# basic-inline-turbidimeter_power_board.net
KiCad netlist of a schematic drawn in EAGLE
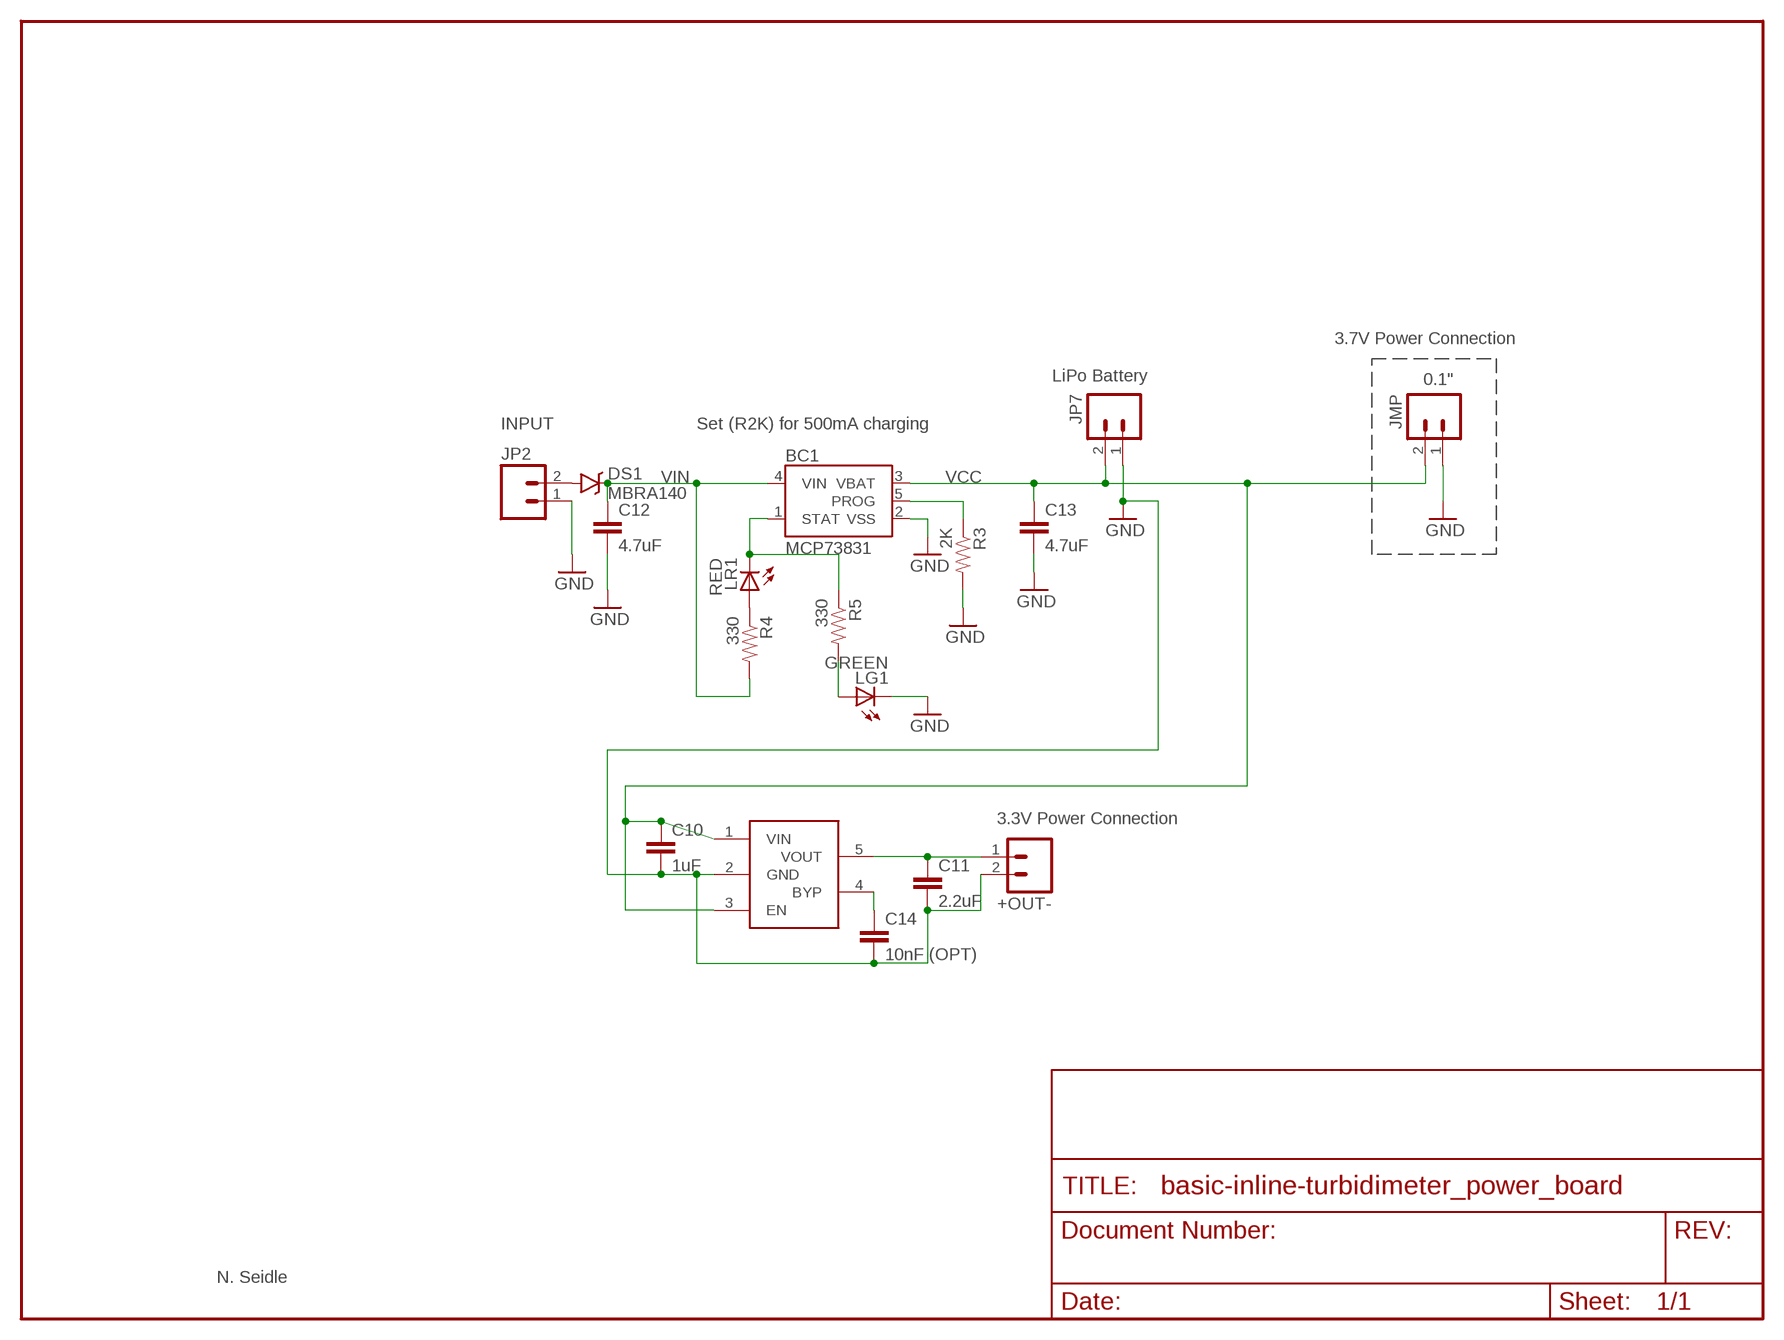
[diagram p0: schematic, sheet 1]

(export (version "E")
  (design (tool "Eeschema 10.0.6"))
  (components
    (comp (ref "+OUT-")
      (value "M02PTH")
      (footprint "eagle-import:1X02")
      (libsource (lib "eagle-import") (part "SparkFun-Connectors_M02PTH"))
    )
    (comp (ref "BC1")
      (value "MCP73831")
      (footprint "eagle-import:SOT23-5")
      (libsource (lib "eagle-import") (part "MCP73831"))
    )
    (comp (ref "C10")
      (value "1uF")
      (footprint "eagle-import:0603-CAP")
      (libsource (lib "eagle-import") (part "SparkFun-Passives_CAP0603-CAP"))
    )
    (comp (ref "C11")
      (value "2.2uF")
      (footprint "eagle-import:0603-CAP")
      (libsource (lib "eagle-import") (part "SparkFun-Passives_CAP0603-CAP"))
    )
    (comp (ref "C12")
      (value "4.7uF")
      (footprint "eagle-import:0402-CAP")
      (libsource (lib "eagle-import") (part "CAP0402-CAP"))
    )
    (comp (ref "C13")
      (value "4.7uF")
      (footprint "eagle-import:0402-CAP")
      (libsource (lib "eagle-import") (part "CAP0402-CAP"))
    )
    (comp (ref "C14")
      (value "10nF (OPT)")
      (footprint "eagle-import:0603-CAP")
      (libsource (lib "eagle-import") (part "SparkFun-Passives_CAP0603-CAP"))
    )
    (comp (ref "DS1")
      (value "MBRA140")
      (footprint "eagle-import:SMA-DIODE")
      (libsource (lib "eagle-import") (part "MBRA140"))
    )
    (comp (ref "JMP")
      (value "M02PTH")
      (footprint "eagle-import:1X02")
      (libsource (lib "eagle-import") (part "M02PTH"))
    )
    (comp (ref "JP2")
      (value "M02PTH")
      (footprint "eagle-import:1X02")
      (libsource (lib "eagle-import") (part "SparkFun-Connectors_M02PTH"))
    )
    (comp (ref "JP7")
      (value "LiPo Battery")
      (footprint "eagle-import:JST-2-SMD")
      (libsource (lib "eagle-import") (part "M02-JST-2MM-SMT"))
    )
    (comp (ref "LG1")
      (value "GREEN")
      (footprint "eagle-import:LED-0603")
      (libsource (lib "eagle-import") (part "LED0603"))
    )
    (comp (ref "LR1")
      (value "RED")
      (footprint "eagle-import:LED-0603")
      (libsource (lib "eagle-import") (part "LED0603"))
    )
    (comp (ref "R3")
      (value "2K")
      (footprint "eagle-import:0402-RES")
      (libsource (lib "eagle-import") (part "RESISTOR0402-RES"))
    )
    (comp (ref "R4")
      (value "330")
      (footprint "eagle-import:0402-RES")
      (libsource (lib "eagle-import") (part "RESISTOR0402-RES"))
    )
    (comp (ref "R5")
      (value "330")
      (footprint "eagle-import:0402-RES")
      (libsource (lib "eagle-import") (part "RESISTOR0402-RES"))
    )
    (comp (ref "VR1")
      (value "LP2985")
      (footprint "eagle-import:LP2985")
      (libsource (lib "eagle-import") (part "LP2985"))
    )
  )
  (nets
    (net (code "1") (name "/VCC") (class "Default")
      (node (ref "BC1") (pin "3") (pinfunction "VBAT_3") (pintype "power_in"))
      (node (ref "C10") (pin "1") (pinfunction "1_1") (pintype "passive"))
      (node (ref "C13") (pin "1") (pinfunction "1_1") (pintype "passive"))
      (node (ref "JMP") (pin "2") (pinfunction "2_2") (pintype "passive"))
      (node (ref "JP7") (pin "2") (pinfunction "2_2") (pintype "passive"))
      (node (ref "VR1") (pin "1") (pinfunction "VIN_1") (pintype "bidirectional"))
      (node (ref "VR1") (pin "3") (pinfunction "EN_3") (pintype "bidirectional"))
    )
    (net (code "2") (name "/VIN") (class "Default")
      (node (ref "BC1") (pin "4") (pinfunction "VIN_4") (pintype "power_in"))
      (node (ref "C12") (pin "1") (pinfunction "1_1") (pintype "passive"))
      (node (ref "DS1") (pin "C") (pinfunction "C_C") (pintype "passive"))
      (node (ref "R4") (pin "2") (pinfunction "2_2") (pintype "passive"))
    )
    (net (code "3") (name "GND") (class "Default")
      (node (ref "+OUT-") (pin "2") (pinfunction "2_2") (pintype "passive"))
      (node (ref "BC1") (pin "2") (pinfunction "VSS_2") (pintype "power_in"))
      (node (ref "C10") (pin "2") (pinfunction "2_2") (pintype "passive"))
      (node (ref "C11") (pin "2") (pinfunction "2_2") (pintype "passive"))
      (node (ref "C12") (pin "2") (pinfunction "2_2") (pintype "passive"))
      (node (ref "C13") (pin "2") (pinfunction "2_2") (pintype "passive"))
      (node (ref "C14") (pin "2") (pinfunction "2_2") (pintype "passive"))
      (node (ref "JMP") (pin "1") (pinfunction "1_1") (pintype "passive"))
      (node (ref "JP2") (pin "1") (pinfunction "1_1") (pintype "passive"))
      (node (ref "JP7") (pin "1") (pinfunction "1_1") (pintype "passive"))
      (node (ref "LG1") (pin "C") (pinfunction "C_C") (pintype "passive"))
      (node (ref "R3") (pin "2") (pinfunction "2_2") (pintype "passive"))
      (node (ref "VR1") (pin "2") (pinfunction "GND_2") (pintype "bidirectional"))
    )
    (net (code "4") (name "Net-(BC1-PROG)") (class "Default")
      (node (ref "BC1") (pin "5") (pinfunction "PROG_5") (pintype "input"))
      (node (ref "R3") (pin "1") (pinfunction "1_1") (pintype "passive"))
    )
    (net (code "5") (name "Net-(BC1-STAT)") (class "Default")
      (node (ref "BC1") (pin "1") (pinfunction "STAT_1") (pintype "output"))
      (node (ref "LR1") (pin "C") (pinfunction "C_C") (pintype "passive"))
      (node (ref "R5") (pin "1") (pinfunction "1_1") (pintype "passive"))
    )
    (net (code "6") (name "Net-(DS1-PadA)") (class "Default")
      (node (ref "DS1") (pin "A") (pinfunction "A_A") (pintype "passive"))
      (node (ref "JP2") (pin "2") (pinfunction "2_2") (pintype "passive"))
    )
    (net (code "7") (name "Net-(LG1-PadA)") (class "Default")
      (node (ref "LG1") (pin "A") (pinfunction "A_A") (pintype "passive"))
      (node (ref "R5") (pin "2") (pinfunction "2_2") (pintype "passive"))
    )
    (net (code "8") (name "Net-(LR1-PadA)") (class "Default")
      (node (ref "LR1") (pin "A") (pinfunction "A_A") (pintype "passive"))
      (node (ref "R4") (pin "1") (pinfunction "1_1") (pintype "passive"))
    )
    (net (code "9") (name "Net-(VR1-BYP)") (class "Default")
      (node (ref "C14") (pin "1") (pinfunction "1_1") (pintype "passive"))
      (node (ref "VR1") (pin "4") (pinfunction "BYP_4") (pintype "bidirectional"))
    )
    (net (code "10") (name "Net-(VR1-VOUT)") (class "Default")
      (node (ref "+OUT-") (pin "1") (pinfunction "1_1") (pintype "passive"))
      (node (ref "C11") (pin "1") (pinfunction "1_1") (pintype "passive"))
      (node (ref "VR1") (pin "5") (pinfunction "VOUT_5") (pintype "bidirectional"))
    )
  )
)
